# top.net
KiCad netlist of a schematic drawn in Altium Designer
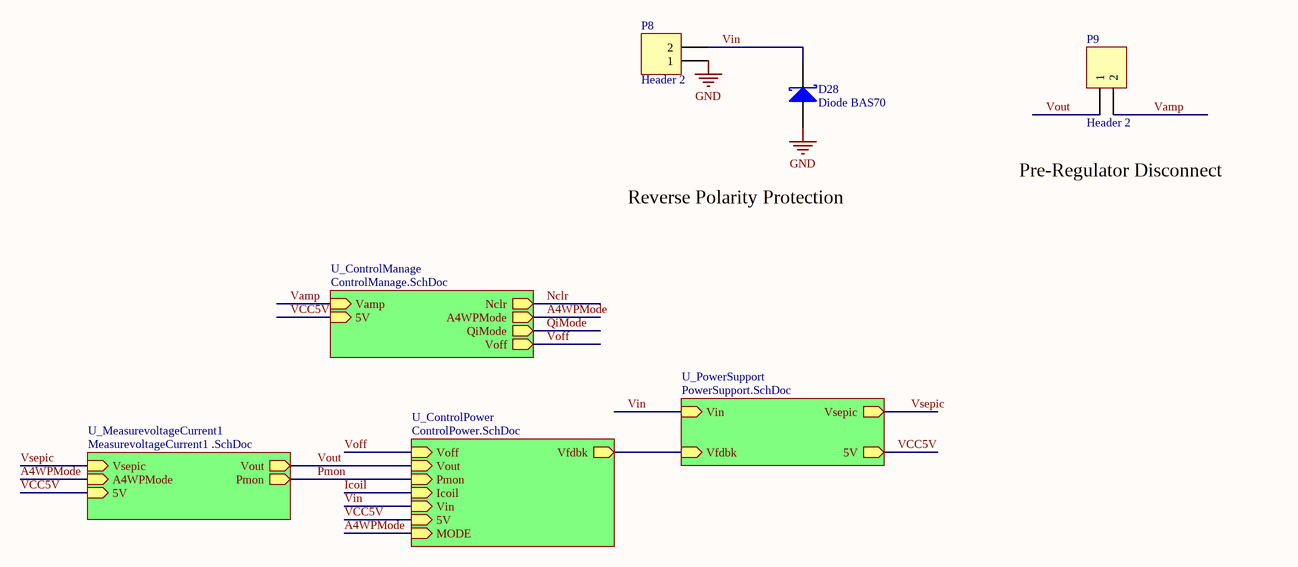
[diagram p0: top.SchDoc]

(export (version "E")
  (design (tool "Eeschema 10.0.6"))
  (components
    (comp (ref "D28")
      (value "Diode BAS70")
      (footprint "SMA")
      (description "Silicon AF Schottky Diode for High-Speed Switching")
      (fields (field (name "PUBLISHER") "Altium Limited"))
      (libsource (lib "Miscellaneous Devices") (part "Diode BAS70"))
    )
    (comp (ref "P8")
      (value "Header 2")
      (footprint "HDR1X2")
      (description "Header, 2-Pin")
      (fields (field (name "PUBLISHER") "Altium Limited"))
      (libsource (lib "Miscellaneous Connectors") (part "Header 2"))
    )
    (comp (ref "P9")
      (value "Header 2")
      (footprint "HDR1X2")
      (description "Header, 2-Pin")
      (fields (field (name "PUBLISHER") "Altium Limited"))
      (libsource (lib "") (part "Header 2_1"))
    )
  )
  (nets
    (net (code "7") (name "/Vamp") (class "Default")
      (node (ref "P9") (pin "2") (pinfunction "2_2") (pintype "passive"))
    )
    (net (code "9") (name "/Vin") (class "Default")
      (node (ref "D28") (pin "3") (pinfunction "K_3") (pintype "passive"))
      (node (ref "P8") (pin "2") (pinfunction "2_2") (pintype "passive"))
    )
    (net (code "11") (name "/Vout") (class "Default")
      (node (ref "P9") (pin "1") (pinfunction "1_1") (pintype "passive"))
    )
    (net (code "13") (name "GND") (class "Default")
      (node (ref "D28") (pin "1") (pinfunction "A_1") (pintype "passive"))
      (node (ref "P8") (pin "1") (pinfunction "1_1") (pintype "passive"))
    )
  )
)
